# MCU.net
KiCad netlist of a schematic drawn in Altium Designer
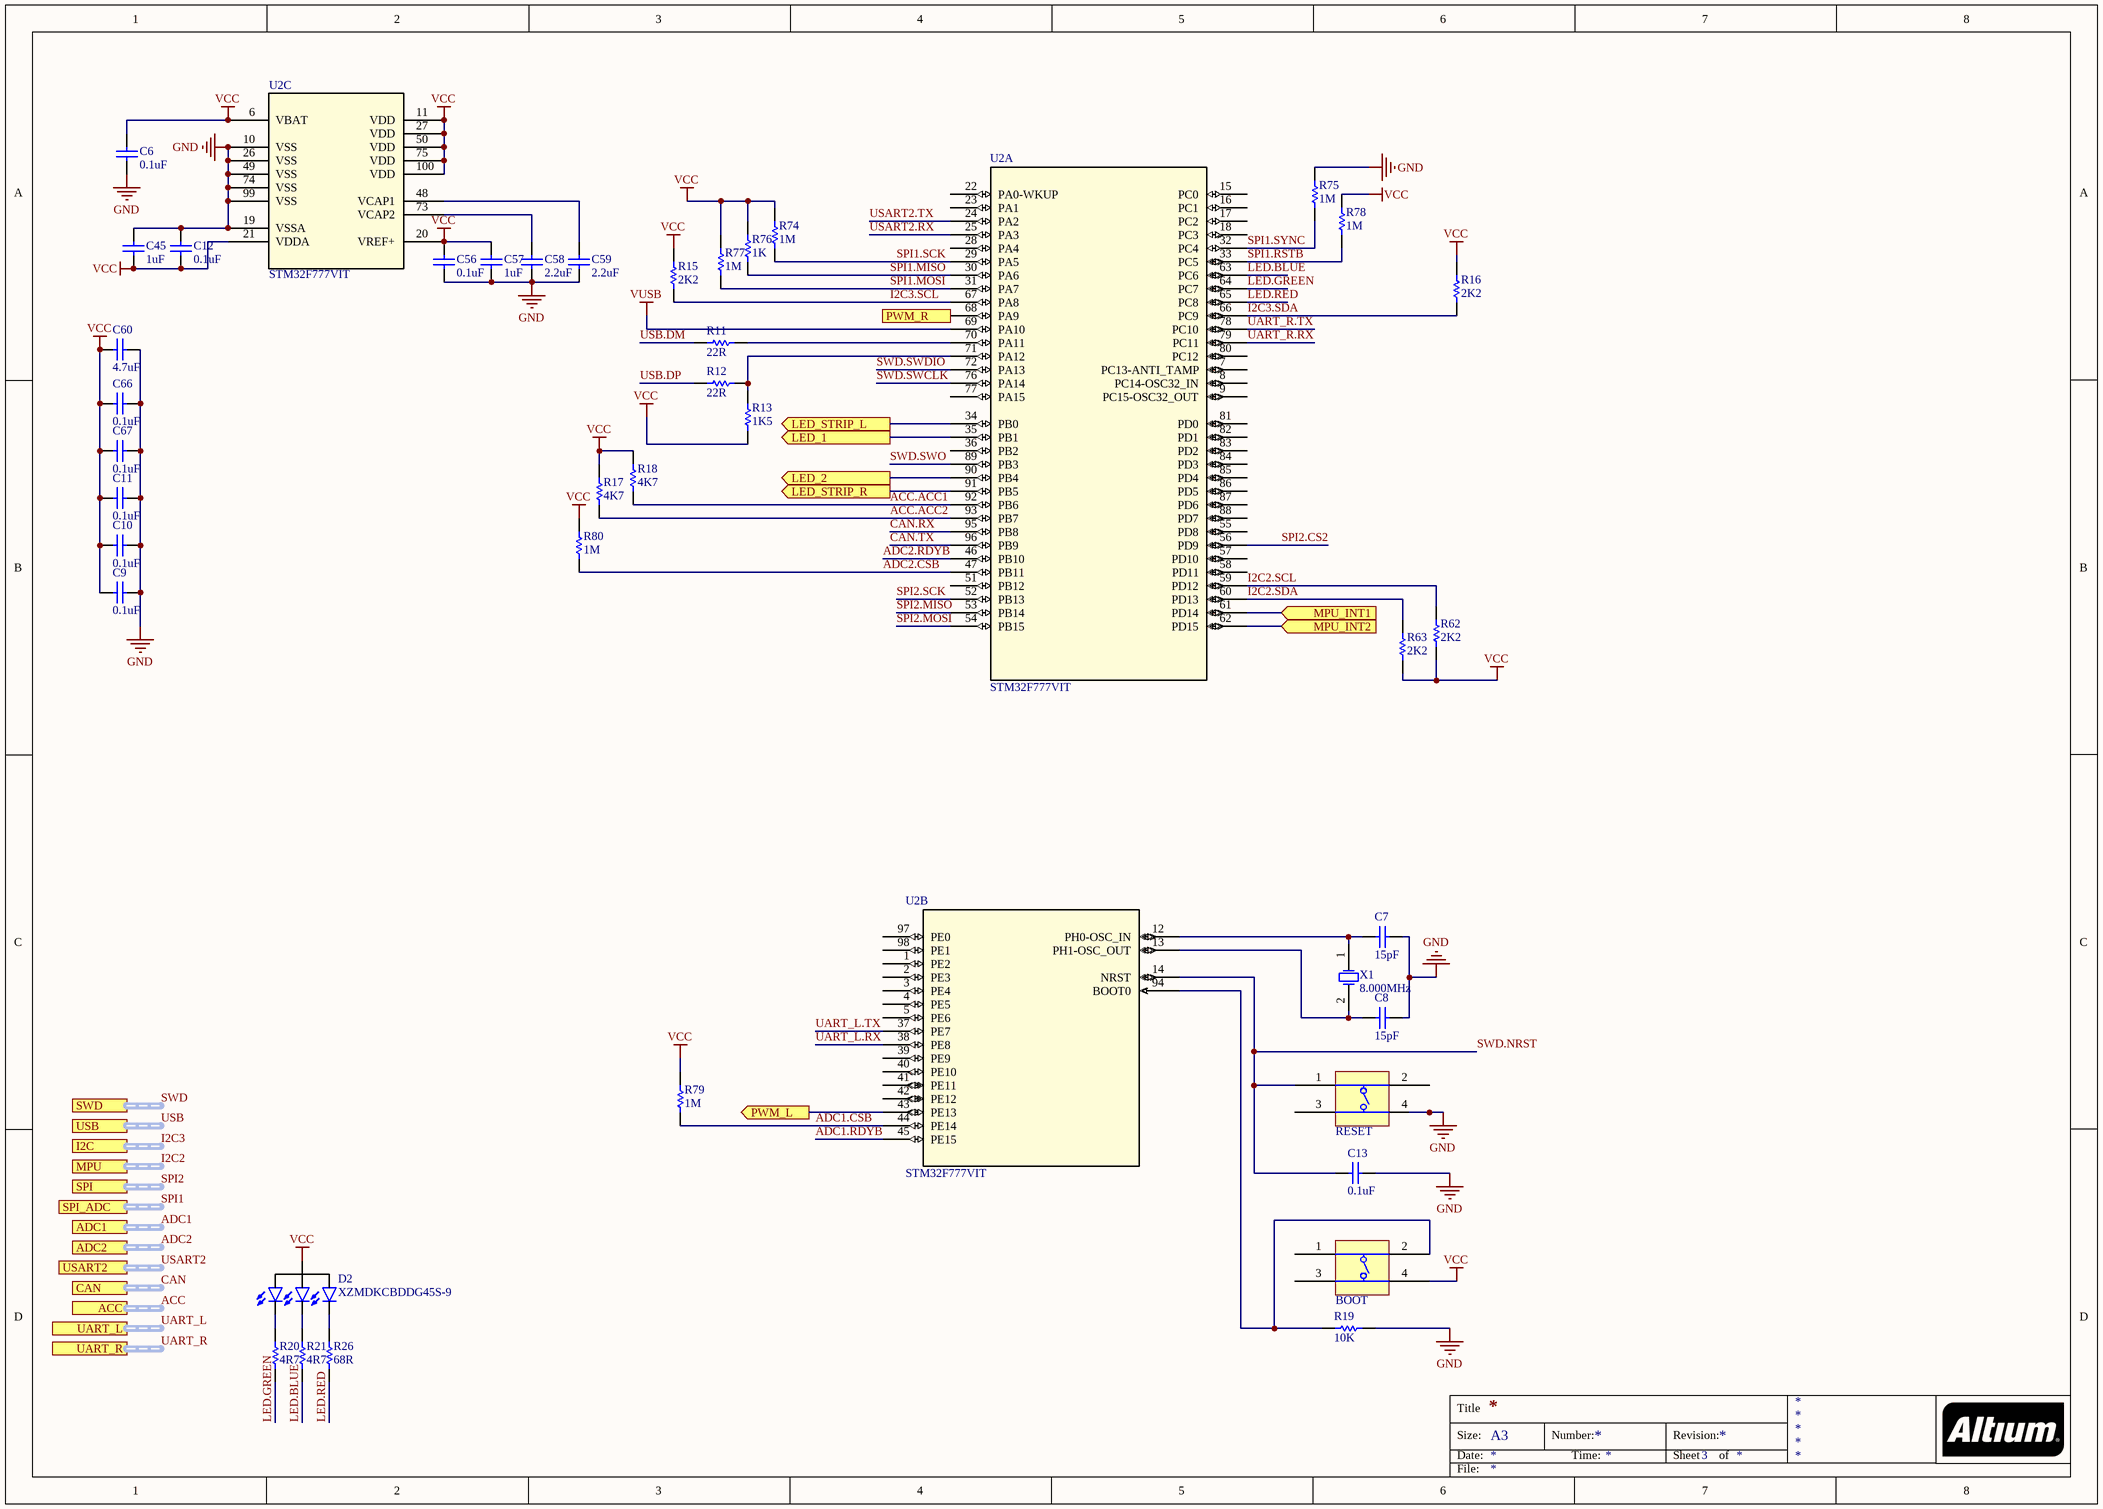
[diagram p0: MCU.SchDoc]

(export (version "E")
  (design (tool "Eeschema 10.0.6"))
  (components
    (comp (ref "BOOT")
      (value "DIPT-DTSM-6")
      (footprint "SWITCH")
      (libsource (lib "Components") (part "DIPT-DTSM-6"))
    )
    (comp (ref "C6")
      (value "0.1uF")
      (footprint "C0603[1608X92]")
      (description "0.1uF 6.3V 10% 0603 (1608 Metric)")
      (fields (field (name "PARTNUMBER") "GRM188R70J104KA01D") (field (name "MANUFACTURER") "Murata"))
      (libsource (lib "Capacitors") (part "CAP_0.1uF_6.3V_0603_10%"))
    )
    (comp (ref "C7")
      (value "15pF")
      (footprint "C0603[1608X92]")
      (description "15pF 6.3V 1% 0603 (1608 Metric)")
      (fields (field (name "PARTNUMBER") "CBR02C150F9GAC") (field (name "MANUFACTURER") "KEMET"))
      (libsource (lib "Capacitors") (part "CAP_15pF_6.3V_0603_1%"))
    )
    (comp (ref "C8")
      (value "15pF")
      (footprint "C0603[1608X92]")
      (description "15pF 6.3V 1% 0603 (1608 Metric)")
      (fields (field (name "PARTNUMBER") "CBR02C150F9GAC") (field (name "MANUFACTURER") "KEMET"))
      (libsource (lib "Capacitors") (part "CAP_15pF_6.3V_0603_1%"))
    )
    (comp (ref "C9")
      (value "0.1uF")
      (footprint "C0603[1608X92]")
      (description "0.1uF 6.3V 10% 0603 (1608 Metric)")
      (fields (field (name "PARTNUMBER") "GRM188R70J104KA01D") (field (name "MANUFACTURER") "Murata"))
      (libsource (lib "Capacitors") (part "CAP_0.1uF_6.3V_0603_10%"))
    )
    (comp (ref "C10")
      (value "0.1uF")
      (footprint "C0603[1608X92]")
      (description "0.1uF 6.3V 10% 0603 (1608 Metric)")
      (fields (field (name "PARTNUMBER") "GRM188R70J104KA01D") (field (name "MANUFACTURER") "Murata"))
      (libsource (lib "Capacitors") (part "CAP_0.1uF_6.3V_0603_10%"))
    )
    (comp (ref "C11")
      (value "0.1uF")
      (footprint "C0603[1608X92]")
      (description "0.1uF 6.3V 10% 0603 (1608 Metric)")
      (fields (field (name "PARTNUMBER") "GRM188R70J104KA01D") (field (name "MANUFACTURER") "Murata"))
      (libsource (lib "Capacitors") (part "CAP_0.1uF_6.3V_0603_10%"))
    )
    (comp (ref "C12")
      (value "0.1uF")
      (footprint "C0603[1608X92]")
      (description "0.1uF 6.3V 10% 0603 (1608 Metric)")
      (fields (field (name "PARTNUMBER") "GRM188R70J104KA01D") (field (name "MANUFACTURER") "Murata"))
      (libsource (lib "Capacitors") (part "CAP_0.1uF_6.3V_0603_10%"))
    )
    (comp (ref "C13")
      (value "0.1uF")
      (footprint "C0603[1608X92]")
      (description "0.1uF 6.3V 10% 0603 (1608 Metric)")
      (fields (field (name "PARTNUMBER") "GRM188R70J104KA01D") (field (name "MANUFACTURER") "Murata"))
      (libsource (lib "Capacitors") (part "CAP_0.1uF_6.3V_0603_10%"))
    )
    (comp (ref "C45")
      (value "1uF")
      (footprint "C0603[1608X92]")
      (description "1uF 6.3V 10% 0603 (1608 Metric)")
      (fields (field (name "PARTNUMBER") "GRM188R60J105KA01D") (field (name "MANUFACTURER") "Murata"))
      (libsource (lib "Capacitors") (part "CAP_1uF_6.3V_0603_10%"))
    )
    (comp (ref "C56")
      (value "0.1uF")
      (footprint "C0603[1608X92]")
      (description "0.1uF 6.3V 10% 0603 (1608 Metric)")
      (fields (field (name "PARTNUMBER") "GRM188R70J104KA01D") (field (name "MANUFACTURER") "Murata"))
      (libsource (lib "Capacitors") (part "CAP_0.1uF_6.3V_0603_10%"))
    )
    (comp (ref "C57")
      (value "1uF")
      (footprint "C0603[1608X92]")
      (description "1uF 6.3V 10% 0603 (1608 Metric)")
      (fields (field (name "PARTNUMBER") "GRM188R60J105KA01D") (field (name "MANUFACTURER") "Murata"))
      (libsource (lib "Capacitors") (part "CAP_1uF_6.3V_0603_10%"))
    )
    (comp (ref "C58")
      (value "2.2uF")
      (footprint "C1206[3216X160]")
      (description "2.2uF 6.3V 10% 1206 (3216 Metric)")
      (fields (field (name "PARTNUMBER") "GRM31CR60J476KE19L") (field (name "MANUFACTURER") "Murata"))
      (libsource (lib "Capacitors") (part "CAP_2.2uF_16V_1206_10%"))
    )
    (comp (ref "C59")
      (value "2.2uF")
      (footprint "C1206[3216X160]")
      (description "2.2uF 6.3V 10% 1206 (3216 Metric)")
      (fields (field (name "PARTNUMBER") "GRM31CR60J476KE19L") (field (name "MANUFACTURER") "Murata"))
      (libsource (lib "Capacitors") (part "CAP_2.2uF_16V_1206_10%"))
    )
    (comp (ref "C60")
      (value "4.7uF")
      (footprint "C0603[1608X92]")
      (description "4.7uF 6.3V 10% 0603 (1608 Metric)")
      (fields (field (name "PARTNUMBER") "GRM188R60J475KE19D") (field (name "MANUFACTURER") "Murata"))
      (libsource (lib "Capacitors") (part "CAP_4.7uF_6.3V_0603_10%"))
    )
    (comp (ref "C66")
      (value "0.1uF")
      (footprint "C0603[1608X92]")
      (description "0.1uF 6.3V 10% 0603 (1608 Metric)")
      (fields (field (name "PARTNUMBER") "GRM188R70J104KA01D") (field (name "MANUFACTURER") "Murata"))
      (libsource (lib "Capacitors") (part "CAP_0.1uF_6.3V_0603_10%"))
    )
    (comp (ref "C67")
      (value "0.1uF")
      (footprint "C0603[1608X92]")
      (description "0.1uF 6.3V 10% 0603 (1608 Metric)")
      (fields (field (name "PARTNUMBER") "GRM188R70J104KA01D") (field (name "MANUFACTURER") "Murata"))
      (libsource (lib "Capacitors") (part "CAP_0.1uF_6.3V_0603_10%"))
    )
    (comp (ref "D2")
      (value "XZMDKCBDDG45S-9")
      (footprint "XZMDKCBDDG45S-9")
      (fields (field (name "MANUFACTURER") "SunLED"))
      (libsource (lib "LEDs") (part "XZMDKCBDDG45S-9"))
    )
    (comp (ref "R11")
      (value "22R")
      (footprint "R0603[1608]")
      (description "22R 0.25W 1% 0603 (1005 Metric)")
      (fields (field (name "MANUFACTURER") "Vishay / Dale") (field (name "PARTNUMBER") "CRCW060322R0FKEAHP"))
      (libsource (lib "Resistors") (part "RES_22R_0603_1%"))
    )
    (comp (ref "R12")
      (value "22R")
      (footprint "R0603[1608]")
      (description "22R 0.25W 1% 0603 (1005 Metric)")
      (fields (field (name "MANUFACTURER") "Vishay / Dale") (field (name "PARTNUMBER") "CRCW060322R0FKEAHP"))
      (libsource (lib "Resistors") (part "RES_22R_0603_1%"))
    )
    (comp (ref "R13")
      (value "1K5")
      (footprint "R0603[1608]")
      (description "1K5 0.25W 1% 0603 (1005 Metric)")
      (fields (field (name "MANUFACTURER") "Vishay / Dale") (field (name "PARTNUMBER") "CRCW06031K50FKEAHP"))
      (libsource (lib "Resistors") (part "RES_1K5_0603_1%"))
    )
    (comp (ref "R15")
      (value "2K2")
      (footprint "R0603[1608]")
      (description "2K2 0.25W 1% 0603 (1005 Metric)")
      (fields (field (name "MANUFACTURER") "Vishay / Dale") (field (name "PARTNUMBER") "CRCW06032K20FKEAHP"))
      (libsource (lib "Resistors") (part "RES_2K2_0603_1%"))
    )
    (comp (ref "R16")
      (value "2K2")
      (footprint "R0603[1608]")
      (description "2K2 0.25W 1% 0603 (1005 Metric)")
      (fields (field (name "MANUFACTURER") "Vishay / Dale") (field (name "PARTNUMBER") "CRCW06032K20FKEAHP"))
      (libsource (lib "Resistors") (part "RES_2K2_0603_1%"))
    )
    (comp (ref "R17")
      (value "4K7")
      (footprint "R0603[1608]")
      (description "4K7 0.25W 1% 0603 (1005 Metric)")
      (fields (field (name "MANUFACTURER") "Vishay / Dale") (field (name "PARTNUMBER") "CRCW06034K70FKEAHP"))
      (libsource (lib "Resistors") (part "RES_4K7_0603_1%"))
    )
    (comp (ref "R18")
      (value "4K7")
      (footprint "R0603[1608]")
      (description "4K7 0.25W 1% 0603 (1005 Metric)")
      (fields (field (name "MANUFACTURER") "Vishay / Dale") (field (name "PARTNUMBER") "CRCW06034K70FKEAHP"))
      (libsource (lib "Resistors") (part "RES_4K7_0603_1%"))
    )
    (comp (ref "R19")
      (value "10K")
      (footprint "R0603[1608]")
      (description "10K 0.25W 1% 0603 (1005 Metric)")
      (fields (field (name "MANUFACTURER") "Vishay") (field (name "PARTNUMBER") "RCS060310K0FKEA"))
      (libsource (lib "Resistors") (part "RES_10K_0603_1%"))
    )
    (comp (ref "R20")
      (value "4R7")
      (footprint "R0603[1608]")
      (description "4R7 0.25W 1% 0603 (1005 Metric)")
      (fields (field (name "MANUFACTURER") "Vishay / Dale") (field (name "PARTNUMBER") "CRCW06034R70JNEAHP"))
      (libsource (lib "Resistors") (part "RES_4R7_0603_1%"))
    )
    (comp (ref "R21")
      (value "4R7")
      (footprint "R0603[1608]")
      (description "4R7 0.25W 1% 0603 (1005 Metric)")
      (fields (field (name "MANUFACTURER") "Vishay / Dale") (field (name "PARTNUMBER") "CRCW06034R70JNEAHP"))
      (libsource (lib "Resistors") (part "RES_4R7_0603_1%"))
    )
    (comp (ref "R26")
      (value "68R")
      (footprint "R0603[1608]")
      (description "68R 0.25W 1% 0603 (1005 Metric)")
      (fields (field (name "MANUFACTURER") "Vishay / Dale") (field (name "PARTNUMBER") "CRCW06036R80FKEAHP"))
      (libsource (lib "Resistors") (part "RES_68R_0603_1%"))
    )
    (comp (ref "R62")
      (value "2K2")
      (footprint "R0603[1608]")
      (description "2K2 0.25W 1% 0603 (1005 Metric)")
      (fields (field (name "MANUFACTURER") "Vishay / Dale") (field (name "PARTNUMBER") "CRCW06032K20FKEAHP"))
      (libsource (lib "Resistors") (part "RES_2K2_0603_1%"))
    )
    (comp (ref "R63")
      (value "2K2")
      (footprint "R0603[1608]")
      (description "2K2 0.25W 1% 0603 (1005 Metric)")
      (fields (field (name "MANUFACTURER") "Vishay / Dale") (field (name "PARTNUMBER") "CRCW06032K20FKEAHP"))
      (libsource (lib "Resistors") (part "RES_2K2_0603_1%"))
    )
    (comp (ref "R74")
      (value "1M")
      (footprint "R0603[1608]")
      (description "1M 0.25W 1% 0603 (1005 Metric)")
      (fields (field (name "MANUFACTURER") "Vishay / Dale") (field (name "PARTNUMBER") "CRCW06031M00JNEAHP"))
      (libsource (lib "Resistors") (part "RES_1M_0603_1%"))
    )
    (comp (ref "R75")
      (value "1M")
      (footprint "R0603[1608]")
      (description "1M 0.25W 1% 0603 (1005 Metric)")
      (fields (field (name "MANUFACTURER") "Vishay / Dale") (field (name "PARTNUMBER") "CRCW06031M00JNEAHP"))
      (libsource (lib "Resistors") (part "RES_1M_0603_1%"))
    )
    (comp (ref "R76")
      (value "1K")
      (footprint "R0603[1608]")
      (description "1K 0.25W 1% 0603 (1005 Metric)")
      (fields (field (name "MANUFACTURER") "Vishay / Dale") (field (name "PARTNUMBER") "CRCW06031K00FKEAHP"))
      (libsource (lib "Resistors") (part "RES_1K_0603_1%"))
    )
    (comp (ref "R77")
      (value "1M")
      (footprint "R0603[1608]")
      (description "1M 0.25W 1% 0603 (1005 Metric)")
      (fields (field (name "MANUFACTURER") "Vishay / Dale") (field (name "PARTNUMBER") "CRCW06031M00JNEAHP"))
      (libsource (lib "Resistors") (part "RES_1M_0603_1%"))
    )
    (comp (ref "R78")
      (value "1M")
      (footprint "R0603[1608]")
      (description "1M 0.25W 1% 0603 (1005 Metric)")
      (fields (field (name "MANUFACTURER") "Vishay / Dale") (field (name "PARTNUMBER") "CRCW06031M00JNEAHP"))
      (libsource (lib "Resistors") (part "RES_1M_0603_1%"))
    )
    (comp (ref "R79")
      (value "1M")
      (footprint "R0603[1608]")
      (description "1M 0.25W 1% 0603 (1005 Metric)")
      (fields (field (name "MANUFACTURER") "Vishay / Dale") (field (name "PARTNUMBER") "CRCW06031M00JNEAHP"))
      (libsource (lib "Resistors") (part "RES_1M_0603_1%"))
    )
    (comp (ref "R80")
      (value "1M")
      (footprint "R0603[1608]")
      (description "1M 0.25W 1% 0603 (1005 Metric)")
      (fields (field (name "MANUFACTURER") "Vishay / Dale") (field (name "PARTNUMBER") "CRCW06031M00JNEAHP"))
      (libsource (lib "Resistors") (part "RES_1M_0603_1%"))
    )
    (comp (ref "RESET")
      (value "DIPT-DTSM-6")
      (footprint "SWITCH")
      (libsource (lib "Components") (part "DIPT-DTSM-6"))
    )
    (comp (ref "U2")
      (value "STM32F777VIT")
      (footprint "LQFP-100_14X14mm")
      (description "Imported")
      (fields (field (name "MANUFACTURER") "STMicroelectronics"))
      (libsource (lib "General_Component") (part "STM32F777VIT"))
    )
    (comp (ref "X1")
      (value "8.000MHz")
      (footprint "OSC_2SM_3R2x2R5")
      (description "Crystal Oscillator")
      (fields (field (name "MANUFACTURER") "NX") (field (name "PARTNUMBER") "NX3225GD-8.000M-EXS00A-CG04874"))
      (libsource (lib "General_Component") (part "XTAL"))
    )
  )
  (nets
    (net (code "14") (name "/ACC.ACC1") (class "Default")
      (node (ref "R18") (pin "1") (pinfunction "1_1") (pintype "passive"))
      (node (ref "U2") (pin "92") (pinfunction "PB6_92") (pintype "bidirectional"))
    )
    (net (code "15") (name "/ACC.ACC2") (class "Default")
      (node (ref "R17") (pin "1") (pinfunction "1_1") (pintype "passive"))
      (node (ref "U2") (pin "93") (pinfunction "PB7_93") (pintype "bidirectional"))
    )
    (net (code "16") (name "/ADC1.CSB") (class "Default")
      (node (ref "R79") (pin "2") (pinfunction "2_2") (pintype "passive"))
      (node (ref "U2") (pin "44") (pinfunction "PE14_44") (pintype "bidirectional"))
    )
    (net (code "17") (name "/ADC1.RDYB") (class "Default")
      (node (ref "U2") (pin "45") (pinfunction "PE15_45") (pintype "bidirectional"))
    )
    (net (code "18") (name "/ADC2.CSB") (class "Default")
      (node (ref "R80") (pin "2") (pinfunction "2_2") (pintype "passive"))
      (node (ref "U2") (pin "47") (pinfunction "PB11_47") (pintype "bidirectional"))
    )
    (net (code "19") (name "/ADC2.RDYB") (class "Default")
      (node (ref "U2") (pin "46") (pinfunction "PB10_46") (pintype "bidirectional"))
    )
    (net (code "20") (name "/CAN.RX") (class "Default")
      (node (ref "U2") (pin "95") (pinfunction "PB8_95") (pintype "bidirectional"))
    )
    (net (code "21") (name "/CAN.TX") (class "Default")
      (node (ref "U2") (pin "96") (pinfunction "PB9_96") (pintype "bidirectional"))
    )
    (net (code "22") (name "/I2C2.SCL") (class "Default")
      (node (ref "R62") (pin "2") (pinfunction "2_2") (pintype "passive"))
      (node (ref "U2") (pin "59") (pinfunction "PD12_59") (pintype "bidirectional"))
    )
    (net (code "23") (name "/I2C2.SDA") (class "Default")
      (node (ref "R63") (pin "2") (pinfunction "2_2") (pintype "passive"))
      (node (ref "U2") (pin "60") (pinfunction "PD13_60") (pintype "bidirectional"))
    )
    (net (code "24") (name "/I2C3.SCL") (class "Default")
      (node (ref "R15") (pin "2") (pinfunction "2_2") (pintype "passive"))
      (node (ref "U2") (pin "67") (pinfunction "PA8_67") (pintype "bidirectional"))
    )
    (net (code "25") (name "/I2C3.SDA") (class "Default")
      (node (ref "R16") (pin "2") (pinfunction "2_2") (pintype "passive"))
      (node (ref "U2") (pin "66") (pinfunction "PC9_66") (pintype "bidirectional"))
    )
    (net (code "26") (name "/LED.BLUE") (class "Default")
      (node (ref "R21") (pin "1") (pinfunction "1_1") (pintype "passive"))
      (node (ref "U2") (pin "63") (pinfunction "PC6_63") (pintype "bidirectional"))
    )
    (net (code "27") (name "/LED.GREEN") (class "Default")
      (node (ref "R20") (pin "1") (pinfunction "1_1") (pintype "passive"))
      (node (ref "U2") (pin "64") (pinfunction "PC7_64") (pintype "bidirectional"))
    )
    (net (code "28") (name "/LED.RED") (class "Default")
      (node (ref "R26") (pin "1") (pinfunction "1_1") (pintype "passive"))
      (node (ref "U2") (pin "65") (pinfunction "PC8_65") (pintype "bidirectional"))
    )
    (net (code "29") (name "/LED_1") (class "Default")
      (node (ref "U2") (pin "35") (pinfunction "PB1_35") (pintype "bidirectional"))
    )
    (net (code "30") (name "/LED_2") (class "Default")
      (node (ref "U2") (pin "90") (pinfunction "PB4_90") (pintype "bidirectional"))
    )
    (net (code "31") (name "/LED_STRIP_L") (class "Default")
      (node (ref "U2") (pin "34") (pinfunction "PB0_34") (pintype "bidirectional"))
    )
    (net (code "32") (name "/LED_STRIP_R") (class "Default")
      (node (ref "U2") (pin "91") (pinfunction "PB5_91") (pintype "bidirectional"))
    )
    (net (code "33") (name "/MPU_INT1") (class "Default")
      (node (ref "U2") (pin "61") (pinfunction "PD14_61") (pintype "bidirectional"))
    )
    (net (code "34") (name "/MPU_INT2") (class "Default")
      (node (ref "U2") (pin "62") (pinfunction "PD15_62") (pintype "bidirectional"))
    )
    (net (code "35") (name "/PWM_L") (class "Default")
      (node (ref "U2") (pin "43") (pinfunction "PE13_43") (pintype "bidirectional"))
    )
    (net (code "36") (name "/PWM_R") (class "Default")
      (node (ref "U2") (pin "68") (pinfunction "PA9_68") (pintype "bidirectional"))
    )
    (net (code "37") (name "/SPI1.MISO") (class "Default")
      (node (ref "R76") (pin "2") (pinfunction "2_2") (pintype "passive"))
      (node (ref "U2") (pin "30") (pinfunction "PA6_30") (pintype "bidirectional"))
    )
    (net (code "38") (name "/SPI1.MOSI") (class "Default")
      (node (ref "R77") (pin "2") (pinfunction "2_2") (pintype "passive"))
      (node (ref "U2") (pin "31") (pinfunction "PA7_31") (pintype "bidirectional"))
    )
    (net (code "39") (name "/SPI1.RSTB") (class "Default")
      (node (ref "R78") (pin "1") (pinfunction "1_1") (pintype "passive"))
      (node (ref "U2") (pin "33") (pinfunction "PC5_33") (pintype "bidirectional"))
    )
    (net (code "40") (name "/SPI1.SCK") (class "Default")
      (node (ref "R74") (pin "2") (pinfunction "2_2") (pintype "passive"))
      (node (ref "U2") (pin "29") (pinfunction "PA5_29") (pintype "bidirectional"))
    )
    (net (code "41") (name "/SPI1.SYNC") (class "Default")
      (node (ref "R75") (pin "1") (pinfunction "1_1") (pintype "passive"))
      (node (ref "U2") (pin "32") (pinfunction "PC4_32") (pintype "bidirectional"))
    )
    (net (code "42") (name "/SPI2.CS2") (class "Default")
      (node (ref "U2") (pin "56") (pinfunction "PD9_56") (pintype "bidirectional"))
    )
    (net (code "43") (name "/SPI2.MISO") (class "Default")
      (node (ref "U2") (pin "53") (pinfunction "PB14_53") (pintype "bidirectional"))
    )
    (net (code "44") (name "/SPI2.MOSI") (class "Default")
      (node (ref "U2") (pin "54") (pinfunction "PB15_54") (pintype "bidirectional"))
    )
    (net (code "45") (name "/SPI2.SCK") (class "Default")
      (node (ref "U2") (pin "52") (pinfunction "PB13_52") (pintype "bidirectional"))
    )
    (net (code "46") (name "/SWD.NRST") (class "Default")
      (node (ref "C13") (pin "1") (pinfunction "1_1") (pintype "passive"))
      (node (ref "RESET") (pin "1") (pinfunction "1_1") (pintype "passive"))
      (node (ref "U2") (pin "14") (pinfunction "NRST_14") (pintype "bidirectional"))
    )
    (net (code "47") (name "/SWD.SWCLK") (class "Default")
      (node (ref "U2") (pin "76") (pinfunction "PA14_76") (pintype "bidirectional"))
    )
    (net (code "48") (name "/SWD.SWDIO") (class "Default")
      (node (ref "U2") (pin "72") (pinfunction "PA13_72") (pintype "bidirectional"))
    )
    (net (code "49") (name "/SWD.SWO") (class "Default")
      (node (ref "U2") (pin "89") (pinfunction "PB3_89") (pintype "bidirectional"))
    )
    (net (code "50") (name "/UART_L.RX") (class "Default")
      (node (ref "U2") (pin "38") (pinfunction "PE8_38") (pintype "bidirectional"))
    )
    (net (code "51") (name "/UART_L.TX") (class "Default")
      (node (ref "U2") (pin "37") (pinfunction "PE7_37") (pintype "bidirectional"))
    )
    (net (code "52") (name "/UART_R.RX") (class "Default")
      (node (ref "U2") (pin "79") (pinfunction "PC11_79") (pintype "bidirectional"))
    )
    (net (code "53") (name "/UART_R.TX") (class "Default")
      (node (ref "U2") (pin "78") (pinfunction "PC10_78") (pintype "bidirectional"))
    )
    (net (code "54") (name "/USART2.RX") (class "Default")
      (node (ref "U2") (pin "25") (pinfunction "PA3_25") (pintype "bidirectional"))
    )
    (net (code "55") (name "/USART2.TX") (class "Default")
      (node (ref "U2") (pin "24") (pinfunction "PA2_24") (pintype "bidirectional"))
    )
    (net (code "56") (name "/USB.DM") (class "Default")
      (node (ref "R11") (pin "1") (pinfunction "1_1") (pintype "passive"))
    )
    (net (code "57") (name "/USB.DP") (class "Default")
      (node (ref "R12") (pin "1") (pinfunction "1_1") (pintype "passive"))
    )
    (net (code "71") (name "GND") (class "Default")
      (node (ref "C10") (pin "2") (pinfunction "2_2") (pintype "passive"))
      (node (ref "C11") (pin "2") (pinfunction "2_2") (pintype "passive"))
      (node (ref "C12") (pin "2") (pinfunction "2_2") (pintype "passive"))
      (node (ref "C13") (pin "2") (pinfunction "2_2") (pintype "passive"))
      (node (ref "C45") (pin "2") (pinfunction "2_2") (pintype "passive"))
      (node (ref "C56") (pin "1") (pinfunction "1_1") (pintype "passive"))
      (node (ref "C57") (pin "1") (pinfunction "1_1") (pintype "passive"))
      (node (ref "C58") (pin "1") (pinfunction "1_1") (pintype "passive"))
      (node (ref "C59") (pin "1") (pinfunction "1_1") (pintype "passive"))
      (node (ref "C6") (pin "1") (pinfunction "1_1") (pintype "passive"))
      (node (ref "C60") (pin "2") (pinfunction "2_2") (pintype "passive"))
      (node (ref "C66") (pin "2") (pinfunction "2_2") (pintype "passive"))
      (node (ref "C67") (pin "2") (pinfunction "2_2") (pintype "passive"))
      (node (ref "C7") (pin "2") (pinfunction "2_2") (pintype "passive"))
      (node (ref "C8") (pin "2") (pinfunction "2_2") (pintype "passive"))
      (node (ref "C9") (pin "2") (pinfunction "2_2") (pintype "passive"))
      (node (ref "R19") (pin "2") (pinfunction "2_2") (pintype "passive"))
      (node (ref "R75") (pin "2") (pinfunction "2_2") (pintype "passive"))
      (node (ref "RESET") (pin "4") (pinfunction "4_4") (pintype "passive"))
      (node (ref "U2") (pin "10") (pinfunction "VSS_10") (pintype "power_in"))
      (node (ref "U2") (pin "19") (pinfunction "VSSA_19") (pintype "power_in"))
      (node (ref "U2") (pin "26") (pinfunction "VSS_26") (pintype "power_in"))
      (node (ref "U2") (pin "49") (pinfunction "VSS_49") (pintype "power_in"))
      (node (ref "U2") (pin "74") (pinfunction "VSS_74") (pintype "power_in"))
      (node (ref "U2") (pin "99") (pinfunction "VSS_99") (pintype "power_in"))
    )
    (net (code "72") (name "Net-(D2-K_Blue)") (class "Default")
      (node (ref "D2") (pin "3") (pinfunction "K_Blue_3") (pintype "passive"))
      (node (ref "R21") (pin "2") (pinfunction "2_2") (pintype "passive"))
    )
    (net (code "73") (name "Net-(D2-K_Green)") (class "Default")
      (node (ref "D2") (pin "4") (pinfunction "K_Green_4") (pintype "passive"))
      (node (ref "R20") (pin "2") (pinfunction "2_2") (pintype "passive"))
    )
    (net (code "74") (name "Net-(D2-K_Red)") (class "Default")
      (node (ref "D2") (pin "1") (pinfunction "K_Red_1") (pintype "passive"))
      (node (ref "R26") (pin "2") (pinfunction "2_2") (pintype "passive"))
    )
    (net (code "75") (name "Net-(U2A-PA11)") (class "Default")
      (node (ref "R11") (pin "2") (pinfunction "2_2") (pintype "passive"))
      (node (ref "U2") (pin "70") (pinfunction "PA11_70") (pintype "bidirectional"))
    )
    (net (code "76") (name "Net-(U2A-PA12)") (class "Default")
      (node (ref "R12") (pin "2") (pinfunction "2_2") (pintype "passive"))
      (node (ref "R13") (pin "2") (pinfunction "2_2") (pintype "passive"))
      (node (ref "U2") (pin "71") (pinfunction "PA12_71") (pintype "bidirectional"))
    )
    (net (code "77") (name "Net-(U2B-BOOT0)") (class "Default")
      (node (ref "BOOT") (pin "2") (pinfunction "2_2") (pintype "passive"))
      (node (ref "R19") (pin "1") (pinfunction "1_1") (pintype "passive"))
      (node (ref "U2") (pin "94") (pinfunction "BOOT0_94") (pintype "input"))
    )
    (net (code "78") (name "Net-(U2B-PH0-OSC_IN)") (class "Default")
      (node (ref "C7") (pin "1") (pinfunction "1_1") (pintype "passive"))
      (node (ref "U2") (pin "12") (pinfunction "PH0-OSC_IN_12") (pintype "bidirectional"))
      (node (ref "X1") (pin "1") (pinfunction "OSC1_1") (pintype "passive"))
    )
    (net (code "79") (name "Net-(U2B-PH1-OSC_OUT)") (class "Default")
      (node (ref "C8") (pin "1") (pinfunction "1_1") (pintype "passive"))
      (node (ref "U2") (pin "13") (pinfunction "PH1-OSC_OUT_13") (pintype "bidirectional"))
      (node (ref "X1") (pin "2") (pinfunction "OSC2_2") (pintype "passive"))
    )
    (net (code "80") (name "Net-(U2C-VCAP1)") (class "Default")
      (node (ref "C59") (pin "2") (pinfunction "2_2") (pintype "passive"))
      (node (ref "U2") (pin "48") (pinfunction "VCAP1_48") (pintype "power_in"))
    )
    (net (code "81") (name "Net-(U2C-VCAP2)") (class "Default")
      (node (ref "C58") (pin "2") (pinfunction "2_2") (pintype "passive"))
      (node (ref "U2") (pin "73") (pinfunction "VCAP2_73") (pintype "power_in"))
    )
    (net (code "82") (name "VCC") (class "Default")
      (node (ref "BOOT") (pin "4") (pinfunction "4_4") (pintype "passive"))
      (node (ref "C10") (pin "1") (pinfunction "1_1") (pintype "passive"))
      (node (ref "C11") (pin "1") (pinfunction "1_1") (pintype "passive"))
      (node (ref "C12") (pin "1") (pinfunction "1_1") (pintype "passive"))
      (node (ref "C45") (pin "1") (pinfunction "1_1") (pintype "passive"))
      (node (ref "C56") (pin "2") (pinfunction "2_2") (pintype "passive"))
      (node (ref "C57") (pin "2") (pinfunction "2_2") (pintype "passive"))
      (node (ref "C6") (pin "2") (pinfunction "2_2") (pintype "passive"))
      (node (ref "C60") (pin "1") (pinfunction "1_1") (pintype "passive"))
      (node (ref "C66") (pin "1") (pinfunction "1_1") (pintype "passive"))
      (node (ref "C67") (pin "1") (pinfunction "1_1") (pintype "passive"))
      (node (ref "C9") (pin "1") (pinfunction "1_1") (pintype "passive"))
      (node (ref "D2") (pin "2") (pinfunction "A_2") (pintype "passive"))
      (node (ref "R13") (pin "1") (pinfunction "1_1") (pintype "passive"))
      (node (ref "R15") (pin "1") (pinfunction "1_1") (pintype "passive"))
      (node (ref "R16") (pin "1") (pinfunction "1_1") (pintype "passive"))
      (node (ref "R17") (pin "2") (pinfunction "2_2") (pintype "passive"))
      (node (ref "R18") (pin "2") (pinfunction "2_2") (pintype "passive"))
      (node (ref "R62") (pin "1") (pinfunction "1_1") (pintype "passive"))
      (node (ref "R63") (pin "1") (pinfunction "1_1") (pintype "passive"))
      (node (ref "R74") (pin "1") (pinfunction "1_1") (pintype "passive"))
      (node (ref "R76") (pin "1") (pinfunction "1_1") (pintype "passive"))
      (node (ref "R77") (pin "1") (pinfunction "1_1") (pintype "passive"))
      (node (ref "R78") (pin "2") (pinfunction "2_2") (pintype "passive"))
      (node (ref "R79") (pin "1") (pinfunction "1_1") (pintype "passive"))
      (node (ref "R80") (pin "1") (pinfunction "1_1") (pintype "passive"))
      (node (ref "U2") (pin "100") (pinfunction "VDD_100") (pintype "power_in"))
      (node (ref "U2") (pin "11") (pinfunction "VDD_11") (pintype "power_in"))
      (node (ref "U2") (pin "20") (pinfunction "VREF+_20") (pintype "power_in"))
      (node (ref "U2") (pin "21") (pinfunction "VDDA_21") (pintype "power_in"))
      (node (ref "U2") (pin "27") (pinfunction "VDD_27") (pintype "power_in"))
      (node (ref "U2") (pin "50") (pinfunction "VDD_50") (pintype "power_in"))
      (node (ref "U2") (pin "6") (pinfunction "VBAT_6") (pintype "power_in"))
      (node (ref "U2") (pin "75") (pinfunction "VDD_75") (pintype "power_in"))
    )
    (net (code "83") (name "VUSB") (class "Default")
      (node (ref "U2") (pin "69") (pinfunction "PA10_69") (pintype "bidirectional"))
    )
    (net (code "84") (name "unconnected-(BOOT-Pad1)") (class "Default")
      (node (ref "BOOT") (pin "1") (pinfunction "1_1") (pintype "passive"))
    )
    (net (code "85") (name "unconnected-(BOOT-Pad3)") (class "Default")
      (node (ref "BOOT") (pin "3") (pinfunction "3_3") (pintype "passive"))
    )
    (net (code "86") (name "unconnected-(RESET-Pad2)") (class "Default")
      (node (ref "RESET") (pin "2") (pinfunction "2_2") (pintype "passive"))
    )
    (net (code "87") (name "unconnected-(RESET-Pad3)") (class "Default")
      (node (ref "RESET") (pin "3") (pinfunction "3_3") (pintype "passive"))
    )
    (net (code "88") (name "unconnected-(U2A-PA0-WKUP-Pad22)") (class "Default")
      (node (ref "U2") (pin "22") (pinfunction "PA0-WKUP_22") (pintype "bidirectional"))
    )
    (net (code "89") (name "unconnected-(U2A-PA1-Pad23)") (class "Default")
      (node (ref "U2") (pin "23") (pinfunction "PA1_23") (pintype "bidirectional"))
    )
    (net (code "90") (name "unconnected-(U2A-PA4-Pad28)") (class "Default")
      (node (ref "U2") (pin "28") (pinfunction "PA4_28") (pintype "bidirectional"))
    )
    (net (code "91") (name "unconnected-(U2A-PA15-Pad77)") (class "Default")
      (node (ref "U2") (pin "77") (pinfunction "PA15_77") (pintype "bidirectional"))
    )
    (net (code "92") (name "unconnected-(U2A-PB2-Pad36)") (class "Default")
      (node (ref "U2") (pin "36") (pinfunction "PB2_36") (pintype "bidirectional"))
    )
    (net (code "93") (name "unconnected-(U2A-PB12-Pad51)") (class "Default")
      (node (ref "U2") (pin "51") (pinfunction "PB12_51") (pintype "bidirectional"))
    )
    (net (code "94") (name "unconnected-(U2A-PC0-Pad15)") (class "Default")
      (node (ref "U2") (pin "15") (pinfunction "PC0_15") (pintype "bidirectional"))
    )
    (net (code "95") (name "unconnected-(U2A-PC1-Pad16)") (class "Default")
      (node (ref "U2") (pin "16") (pinfunction "PC1_16") (pintype "bidirectional"))
    )
    (net (code "96") (name "unconnected-(U2A-PC2-Pad17)") (class "Default")
      (node (ref "U2") (pin "17") (pinfunction "PC2_17") (pintype "bidirectional"))
    )
    (net (code "97") (name "unconnected-(U2A-PC3-Pad18)") (class "Default")
      (node (ref "U2") (pin "18") (pinfunction "PC3_18") (pintype "bidirectional"))
    )
    (net (code "98") (name "unconnected-(U2A-PC12-Pad80)") (class "Default")
      (node (ref "U2") (pin "80") (pinfunction "PC12_80") (pintype "bidirectional"))
    )
    (net (code "99") (name "unconnected-(U2A-PC13-ANTI_TAMP-Pad7)") (class "Default")
      (node (ref "U2") (pin "7") (pinfunction "PC13-ANTI_TAMP_7") (pintype "bidirectional"))
    )
    (net (code "100") (name "unconnected-(U2A-PC14-OSC32_IN-Pad8)") (class "Default")
      (node (ref "U2") (pin "8") (pinfunction "PC14-OSC32_IN_8") (pintype "bidirectional"))
    )
    (net (code "101") (name "unconnected-(U2A-PC15-OSC32_OUT-Pad9)") (class "Default")
      (node (ref "U2") (pin "9") (pinfunction "PC15-OSC32_OUT_9") (pintype "bidirectional"))
    )
    (net (code "102") (name "unconnected-(U2A-PD0-Pad81)") (class "Default")
      (node (ref "U2") (pin "81") (pinfunction "PD0_81") (pintype "bidirectional"))
    )
    (net (code "103") (name "unconnected-(U2A-PD1-Pad82)") (class "Default")
      (node (ref "U2") (pin "82") (pinfunction "PD1_82") (pintype "bidirectional"))
    )
    (net (code "104") (name "unconnected-(U2A-PD2-Pad83)") (class "Default")
      (node (ref "U2") (pin "83") (pinfunction "PD2_83") (pintype "bidirectional"))
    )
    (net (code "105") (name "unconnected-(U2A-PD3-Pad84)") (class "Default")
      (node (ref "U2") (pin "84") (pinfunction "PD3_84") (pintype "bidirectional"))
    )
    (net (code "106") (name "unconnected-(U2A-PD4-Pad85)") (class "Default")
      (node (ref "U2") (pin "85") (pinfunction "PD4_85") (pintype "bidirectional"))
    )
    (net (code "107") (name "unconnected-(U2A-PD5-Pad86)") (class "Default")
      (node (ref "U2") (pin "86") (pinfunction "PD5_86") (pintype "bidirectional"))
    )
    (net (code "108") (name "unconnected-(U2A-PD6-Pad87)") (class "Default")
      (node (ref "U2") (pin "87") (pinfunction "PD6_87") (pintype "bidirectional"))
    )
    (net (code "109") (name "unconnected-(U2A-PD7-Pad88)") (class "Default")
      (node (ref "U2") (pin "88") (pinfunction "PD7_88") (pintype "bidirectional"))
    )
    (net (code "110") (name "unconnected-(U2A-PD8-Pad55)") (class "Default")
      (node (ref "U2") (pin "55") (pinfunction "PD8_55") (pintype "bidirectional"))
    )
    (net (code "111") (name "unconnected-(U2A-PD10-Pad57)") (class "Default")
      (node (ref "U2") (pin "57") (pinfunction "PD10_57") (pintype "bidirectional"))
    )
    (net (code "112") (name "unconnected-(U2A-PD11-Pad58)") (class "Default")
      (node (ref "U2") (pin "58") (pinfunction "PD11_58") (pintype "bidirectional"))
    )
    (net (code "113") (name "unconnected-(U2B-PE0-Pad97)") (class "Default")
      (node (ref "U2") (pin "97") (pinfunction "PE0_97") (pintype "bidirectional"))
    )
    (net (code "114") (name "unconnected-(U2B-PE1-Pad98)") (class "Default")
      (node (ref "U2") (pin "98") (pinfunction "PE1_98") (pintype "bidirectional"))
    )
    (net (code "115") (name "unconnected-(U2B-PE2-Pad1)") (class "Default")
      (node (ref "U2") (pin "1") (pinfunction "PE2_1") (pintype "bidirectional"))
    )
    (net (code "116") (name "unconnected-(U2B-PE3-Pad2)") (class "Default")
      (node (ref "U2") (pin "2") (pinfunction "PE3_2") (pintype "bidirectional"))
    )
    (net (code "117") (name "unconnected-(U2B-PE4-Pad3)") (class "Default")
      (node (ref "U2") (pin "3") (pinfunction "PE4_3") (pintype "bidirectional"))
    )
    (net (code "118") (name "unconnected-(U2B-PE5-Pad4)") (class "Default")
      (node (ref "U2") (pin "4") (pinfunction "PE5_4") (pintype "bidirectional"))
    )
    (net (code "119") (name "unconnected-(U2B-PE6-Pad5)") (class "Default")
      (node (ref "U2") (pin "5") (pinfunction "PE6_5") (pintype "bidirectional"))
    )
    (net (code "120") (name "unconnected-(U2B-PE9-Pad39)") (class "Default")
      (node (ref "U2") (pin "39") (pinfunction "PE9_39") (pintype "bidirectional"))
    )
    (net (code "121") (name "unconnected-(U2B-PE10-Pad40)") (class "Default")
      (node (ref "U2") (pin "40") (pinfunction "PE10_40") (pintype "bidirectional"))
    )
    (net (code "122") (name "unconnected-(U2B-PE11-Pad41)") (class "Default")
      (node (ref "U2") (pin "41") (pinfunction "PE11_41") (pintype "bidirectional"))
    )
    (net (code "123") (name "unconnected-(U2B-PE12-Pad42)") (class "Default")
      (node (ref "U2") (pin "42") (pinfunction "PE12_42") (pintype "bidirectional"))
    )
  )
)
